# EthernetBridge.net
KiCad netlist of a schematic drawn in Altium Designer
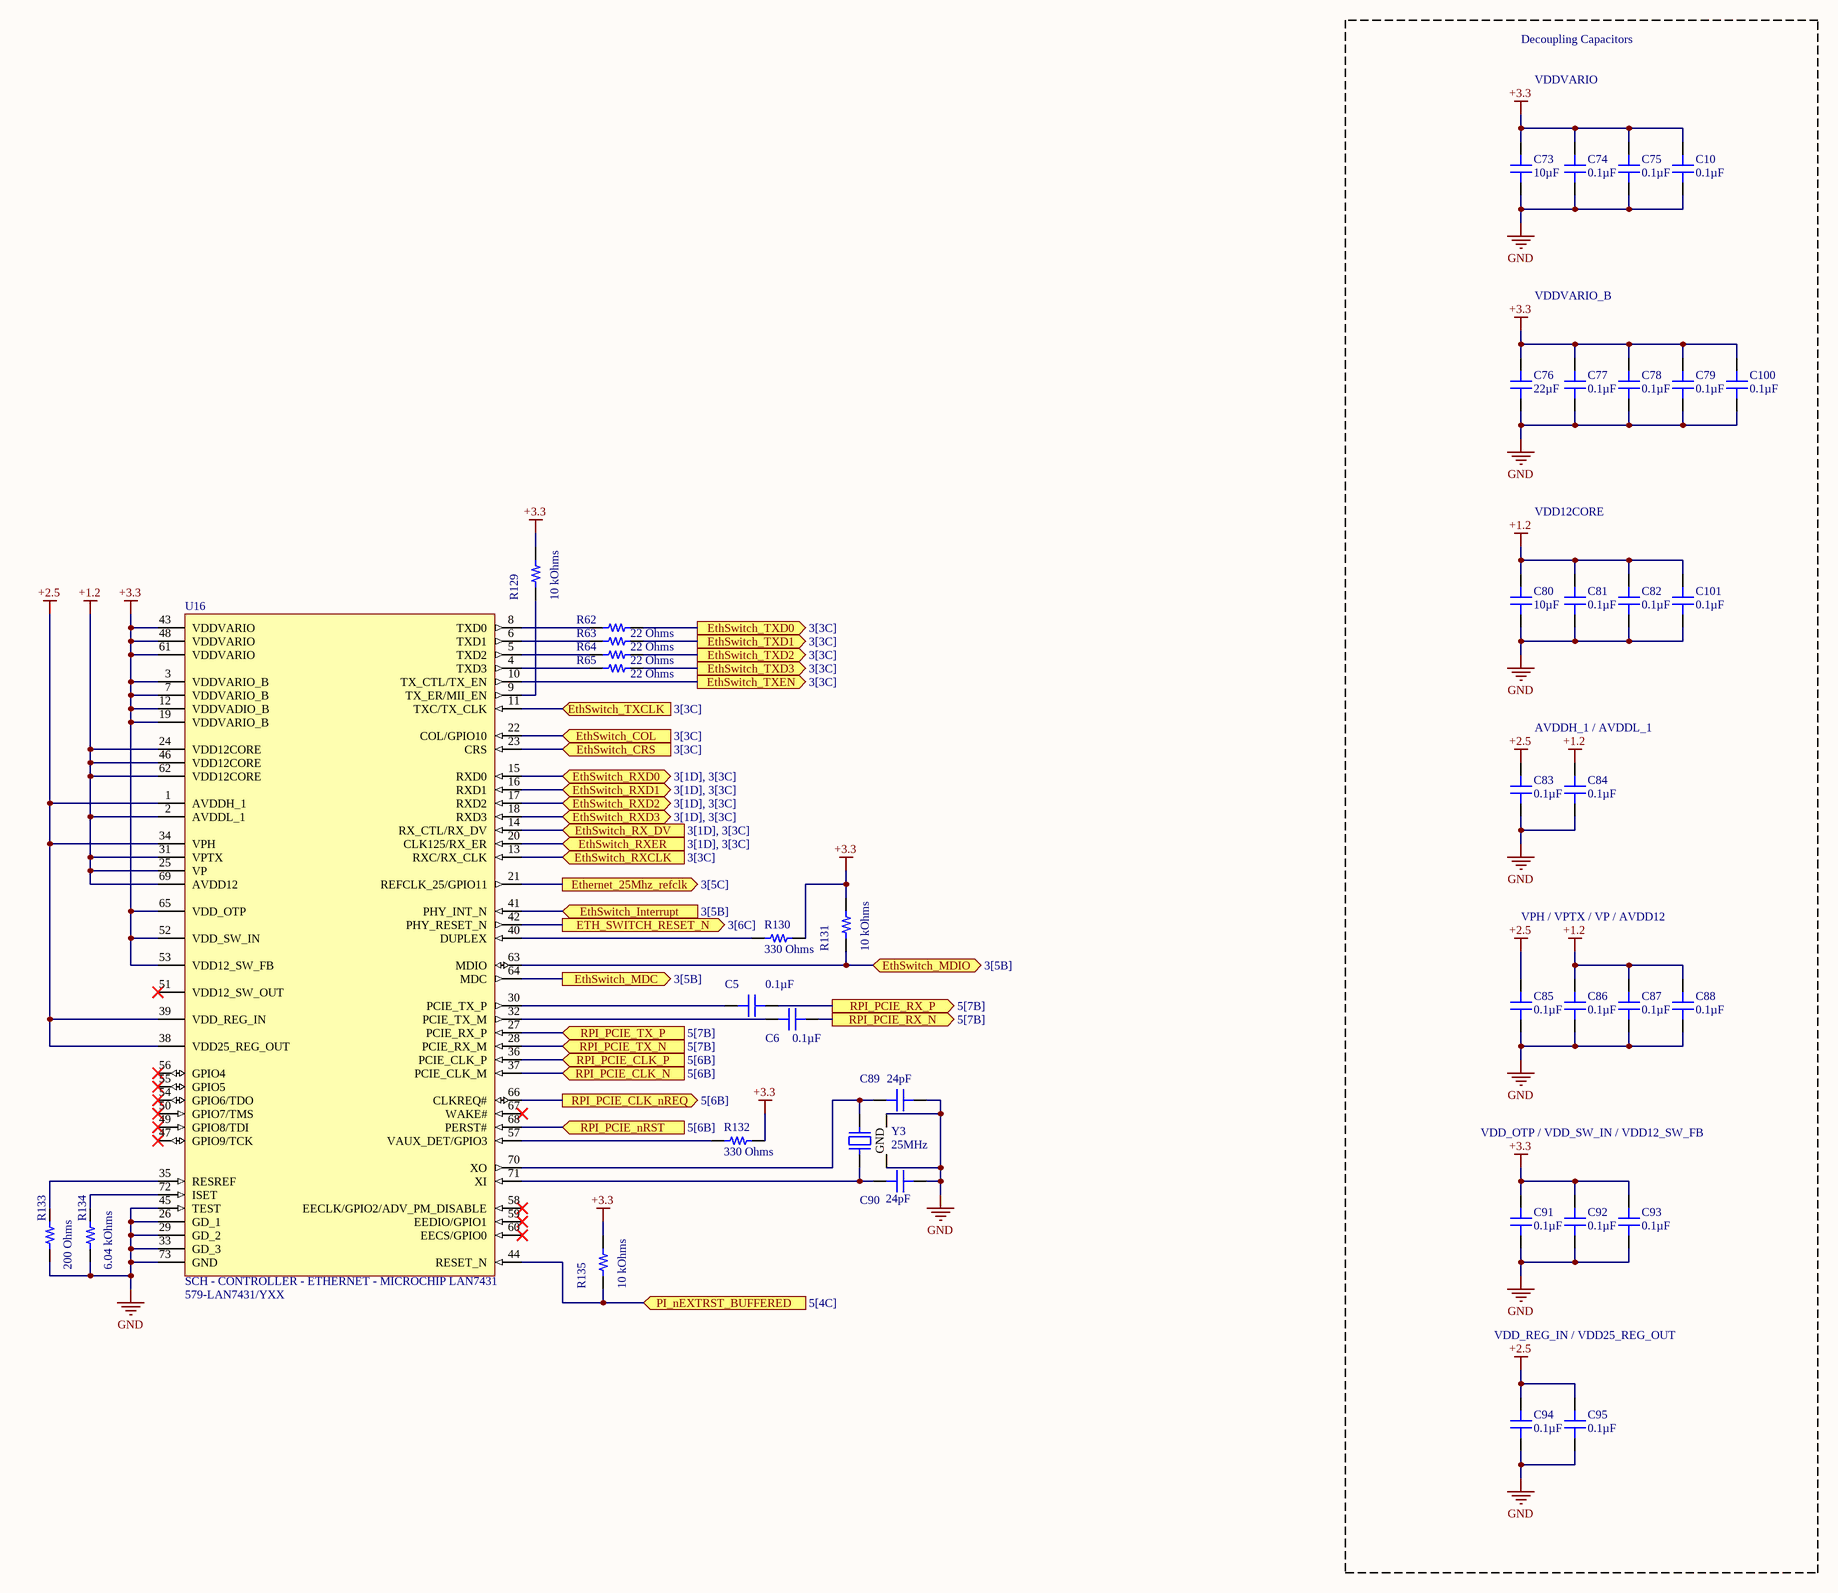
[diagram p0: EthernetBridge.SchDoc]

(export (version "E")
  (design (tool "Eeschema 10.0.6"))
  (components
    (comp (ref "C5")
      (value "0.1µF")
      (footprint "CAP 0603_1608")
      (description "CAP CER 0.1UF 25V X7R 0603")
      (fields
        (field (name "PART NUMBER") "CL10B104KA8WPNC")
        (field (name "MANUFACTURER") "Samsung Electro-Mechanics")
      )
      (libsource (lib "Celestial Altium Library - altium_library") (part "Capacitor"))
    )
    (comp (ref "C6")
      (value "0.1µF")
      (footprint "CAP 0603_1608")
      (description "CAP CER 0.1UF 25V X7R 0603")
      (fields
        (field (name "PART NUMBER") "CL10B104KA8WPNC")
        (field (name "MANUFACTURER") "Samsung Electro-Mechanics")
      )
      (libsource (lib "Celestial Altium Library - altium_library") (part "Capacitor"))
    )
    (comp (ref "C10")
      (value "0.1µF")
      (footprint "CAP 0603_1608")
      (description "CAP CER 0.1UF 25V X7R 0603")
      (fields
        (field (name "PART NUMBER") "CL10B104KA8WPNC")
        (field (name "MANUFACTURER") "Samsung Electro-Mechanics")
      )
      (libsource (lib "Celestial Altium Library - altium_library") (part "Capacitor"))
    )
    (comp (ref "C73")
      (value "10µF")
      (footprint "CAP 0805_2012")
      (description "CAP CER 10UF 16V X5R 0805")
      (fields (field (name "PART NUMBER") "CC0805KKX5R7BB106") (field (name "MANUFACTURER") "Yageo"))
      (libsource (lib "Celestial Altium Library - altium_library") (part "Capacitor"))
    )
    (comp (ref "C74")
      (value "0.1µF")
      (footprint "CAP 0603_1608")
      (description "CAP CER 0.1UF 25V X7R 0603")
      (fields
        (field (name "PART NUMBER") "CL10B104KA8WPNC")
        (field (name "MANUFACTURER") "Samsung Electro-Mechanics")
      )
      (libsource (lib "Celestial Altium Library - altium_library") (part "Capacitor"))
    )
    (comp (ref "C75")
      (value "0.1µF")
      (footprint "CAP 0603_1608")
      (description "CAP CER 0.1UF 25V X7R 0603")
      (fields
        (field (name "PART NUMBER") "CL10B104KA8WPNC")
        (field (name "MANUFACTURER") "Samsung Electro-Mechanics")
      )
      (libsource (lib "Celestial Altium Library - altium_library") (part "Capacitor"))
    )
    (comp (ref "C76")
      (value "22µF")
      (footprint "CAP 0805_2012")
      (description "CAP CER 22UF 10V X5R 0805")
      (fields
        (field (name "PART NUMBER") "CL21A226KPCLRNC")
        (field (name "MANUFACTURER") "Samsung Electro-Mechanics")
      )
      (libsource (lib "Celestial Altium Library - altium_library") (part "Capacitor"))
    )
    (comp (ref "C77")
      (value "0.1µF")
      (footprint "CAP 0603_1608")
      (description "CAP CER 0.1UF 25V X7R 0603")
      (fields
        (field (name "PART NUMBER") "CL10B104KA8WPNC")
        (field (name "MANUFACTURER") "Samsung Electro-Mechanics")
      )
      (libsource (lib "Celestial Altium Library - altium_library") (part "Capacitor"))
    )
    (comp (ref "C78")
      (value "0.1µF")
      (footprint "CAP 0603_1608")
      (description "CAP CER 0.1UF 25V X7R 0603")
      (fields
        (field (name "PART NUMBER") "CL10B104KA8WPNC")
        (field (name "MANUFACTURER") "Samsung Electro-Mechanics")
      )
      (libsource (lib "Celestial Altium Library - altium_library") (part "Capacitor"))
    )
    (comp (ref "C79")
      (value "0.1µF")
      (footprint "CAP 0603_1608")
      (description "CAP CER 0.1UF 25V X7R 0603")
      (fields
        (field (name "PART NUMBER") "CL10B104KA8WPNC")
        (field (name "MANUFACTURER") "Samsung Electro-Mechanics")
      )
      (libsource (lib "Celestial Altium Library - altium_library") (part "Capacitor"))
    )
    (comp (ref "C80")
      (value "10µF")
      (footprint "CAP 0805_2012")
      (description "CAP CER 10UF 16V X5R 0805")
      (fields (field (name "PART NUMBER") "CC0805KKX5R7BB106") (field (name "MANUFACTURER") "Yageo"))
      (libsource (lib "Celestial Altium Library - altium_library") (part "Capacitor"))
    )
    (comp (ref "C81")
      (value "0.1µF")
      (footprint "CAP 0603_1608")
      (description "CAP CER 0.1UF 25V X7R 0603")
      (fields
        (field (name "PART NUMBER") "CL10B104KA8WPNC")
        (field (name "MANUFACTURER") "Samsung Electro-Mechanics")
      )
      (libsource (lib "Celestial Altium Library - altium_library") (part "Capacitor"))
    )
    (comp (ref "C82")
      (value "0.1µF")
      (footprint "CAP 0603_1608")
      (description "CAP CER 0.1UF 25V X7R 0603")
      (fields
        (field (name "PART NUMBER") "CL10B104KA8WPNC")
        (field (name "MANUFACTURER") "Samsung Electro-Mechanics")
      )
      (libsource (lib "Celestial Altium Library - altium_library") (part "Capacitor"))
    )
    (comp (ref "C83")
      (value "0.1µF")
      (footprint "CAP 0603_1608")
      (description "CAP CER 0.1UF 25V X7R 0603")
      (fields
        (field (name "PART NUMBER") "CL10B104KA8WPNC")
        (field (name "MANUFACTURER") "Samsung Electro-Mechanics")
      )
      (libsource (lib "Celestial Altium Library - altium_library") (part "Capacitor"))
    )
    (comp (ref "C84")
      (value "0.1µF")
      (footprint "CAP 0603_1608")
      (description "CAP CER 0.1UF 25V X7R 0603")
      (fields
        (field (name "PART NUMBER") "CL10B104KA8WPNC")
        (field (name "MANUFACTURER") "Samsung Electro-Mechanics")
      )
      (libsource (lib "Celestial Altium Library - altium_library") (part "Capacitor"))
    )
    (comp (ref "C85")
      (value "0.1µF")
      (footprint "CAP 0603_1608")
      (description "CAP CER 0.1UF 25V X7R 0603")
      (fields
        (field (name "PART NUMBER") "CL10B104KA8WPNC")
        (field (name "MANUFACTURER") "Samsung Electro-Mechanics")
      )
      (libsource (lib "Celestial Altium Library - altium_library") (part "Capacitor"))
    )
    (comp (ref "C86")
      (value "0.1µF")
      (footprint "CAP 0603_1608")
      (description "CAP CER 0.1UF 25V X7R 0603")
      (fields
        (field (name "PART NUMBER") "CL10B104KA8WPNC")
        (field (name "MANUFACTURER") "Samsung Electro-Mechanics")
      )
      (libsource (lib "Celestial Altium Library - altium_library") (part "Capacitor"))
    )
    (comp (ref "C87")
      (value "0.1µF")
      (footprint "CAP 0603_1608")
      (description "CAP CER 0.1UF 25V X7R 0603")
      (fields
        (field (name "PART NUMBER") "CL10B104KA8WPNC")
        (field (name "MANUFACTURER") "Samsung Electro-Mechanics")
      )
      (libsource (lib "Celestial Altium Library - altium_library") (part "Capacitor"))
    )
    (comp (ref "C88")
      (value "0.1µF")
      (footprint "CAP 0603_1608")
      (description "CAP CER 0.1UF 25V X7R 0603")
      (fields
        (field (name "PART NUMBER") "CL10B104KA8WPNC")
        (field (name "MANUFACTURER") "Samsung Electro-Mechanics")
      )
      (libsource (lib "Celestial Altium Library - altium_library") (part "Capacitor"))
    )
    (comp (ref "C89")
      (value "24pF")
      (footprint "CAP 0603_1608")
      (description "CAP CER 24PF 50V C0G/NP0 0603")
      (fields
        (field (name "PART NUMBER") "CL10C240JB8NNNC")
        (field (name "MANUFACTURER") "Samsung Electro-Mechanics")
      )
      (libsource (lib "Celestial Altium Library - altium_library") (part "Capacitor"))
    )
    (comp (ref "C90")
      (value "24pF")
      (footprint "CAP 0603_1608")
      (description "CAP CER 24PF 50V C0G/NP0 0603")
      (fields
        (field (name "PART NUMBER") "CL10C240JB8NNNC")
        (field (name "MANUFACTURER") "Samsung Electro-Mechanics")
      )
      (libsource (lib "Celestial Altium Library - altium_library") (part "Capacitor"))
    )
    (comp (ref "C91")
      (value "0.1µF")
      (footprint "CAP 0603_1608")
      (description "CAP CER 0.1UF 25V X7R 0603")
      (fields
        (field (name "PART NUMBER") "CL10B104KA8WPNC")
        (field (name "MANUFACTURER") "Samsung Electro-Mechanics")
      )
      (libsource (lib "Celestial Altium Library - altium_library") (part "Capacitor"))
    )
    (comp (ref "C92")
      (value "0.1µF")
      (footprint "CAP 0603_1608")
      (description "CAP CER 0.1UF 25V X7R 0603")
      (fields
        (field (name "PART NUMBER") "CL10B104KA8WPNC")
        (field (name "MANUFACTURER") "Samsung Electro-Mechanics")
      )
      (libsource (lib "Celestial Altium Library - altium_library") (part "Capacitor"))
    )
    (comp (ref "C93")
      (value "0.1µF")
      (footprint "CAP 0603_1608")
      (description "CAP CER 0.1UF 25V X7R 0603")
      (fields
        (field (name "PART NUMBER") "CL10B104KA8WPNC")
        (field (name "MANUFACTURER") "Samsung Electro-Mechanics")
      )
      (libsource (lib "Celestial Altium Library - altium_library") (part "Capacitor"))
    )
    (comp (ref "C94")
      (value "0.1µF")
      (footprint "CAP 0603_1608")
      (description "CAP CER 0.1UF 25V X7R 0603")
      (fields
        (field (name "PART NUMBER") "CL10B104KA8WPNC")
        (field (name "MANUFACTURER") "Samsung Electro-Mechanics")
      )
      (libsource (lib "Celestial Altium Library - altium_library") (part "Capacitor"))
    )
    (comp (ref "C95")
      (value "0.1µF")
      (footprint "CAP 0603_1608")
      (description "CAP CER 0.1UF 25V X7R 0603")
      (fields
        (field (name "PART NUMBER") "CL10B104KA8WPNC")
        (field (name "MANUFACTURER") "Samsung Electro-Mechanics")
      )
      (libsource (lib "Celestial Altium Library - altium_library") (part "Capacitor"))
    )
    (comp (ref "C100")
      (value "0.1µF")
      (footprint "CAP 0603_1608")
      (description "CAP CER 0.1UF 25V X7R 0603")
      (fields
        (field (name "PART NUMBER") "CL10B104KA8WPNC")
        (field (name "MANUFACTURER") "Samsung Electro-Mechanics")
      )
      (libsource (lib "Celestial Altium Library - altium_library") (part "Capacitor"))
    )
    (comp (ref "C101")
      (value "0.1µF")
      (footprint "CAP 0603_1608")
      (description "CAP CER 0.1UF 25V X7R 0603")
      (fields
        (field (name "PART NUMBER") "CL10B104KA8WPNC")
        (field (name "MANUFACTURER") "Samsung Electro-Mechanics")
      )
      (libsource (lib "Celestial Altium Library - altium_library") (part "Capacitor"))
    )
    (comp (ref "R62")
      (value "22 Ohms")
      (footprint "RES 0603_1608")
      (description "RES 22 OHM 1% 1/10W 0603")
      (fields
        (field (name "PART NUMBER") "RMCF0603FT22R0")
        (field (name "MANUFACTURER") "Stackpole Electronics Inc")
      )
      (libsource (lib "Celestial Altium Library - altium_library") (part "Resistor"))
    )
    (comp (ref "R63")
      (value "22 Ohms")
      (footprint "RES 0603_1608")
      (description "RES 22 OHM 1% 1/10W 0603")
      (fields
        (field (name "PART NUMBER") "RMCF0603FT22R0")
        (field (name "MANUFACTURER") "Stackpole Electronics Inc")
      )
      (libsource (lib "Celestial Altium Library - altium_library") (part "Resistor"))
    )
    (comp (ref "R64")
      (value "22 Ohms")
      (footprint "RES 0603_1608")
      (description "RES 22 OHM 1% 1/10W 0603")
      (fields
        (field (name "PART NUMBER") "RMCF0603FT22R0")
        (field (name "MANUFACTURER") "Stackpole Electronics Inc")
      )
      (libsource (lib "Celestial Altium Library - altium_library") (part "Resistor"))
    )
    (comp (ref "R65")
      (value "22 Ohms")
      (footprint "RES 0603_1608")
      (description "RES 22 OHM 1% 1/10W 0603")
      (fields
        (field (name "PART NUMBER") "RMCF0603FT22R0")
        (field (name "MANUFACTURER") "Stackpole Electronics Inc")
      )
      (libsource (lib "Celestial Altium Library - altium_library") (part "Resistor"))
    )
    (comp (ref "R129")
      (value "10 kOhms")
      (footprint "RES 0603_1608")
      (description "RES 10K OHM 5% 1/10W 0603")
      (fields
        (field (name "PART NUMBER") "RMCF0603JT10K0")
        (field (name "MANUFACTURER") "Stackpole Electronics Inc")
      )
      (libsource (lib "Celestial Altium Library - altium_library") (part "Resistor"))
    )
    (comp (ref "R130")
      (value "330 Ohms")
      (footprint "RES 0603_1608")
      (description "RES 330 OHM 1% 1/10W 0603")
      (fields
        (field (name "PART NUMBER") "RMCF0603FT330R")
        (field (name "MANUFACTURER") "Stackpole Electronics Inc")
      )
      (libsource (lib "Celestial Altium Library - altium_library") (part "Resistor"))
    )
    (comp (ref "R131")
      (value "10 kOhms")
      (footprint "RES 0603_1608")
      (description "RES 10K OHM 5% 1/10W 0603")
      (fields
        (field (name "PART NUMBER") "RMCF0603JT10K0")
        (field (name "MANUFACTURER") "Stackpole Electronics Inc")
      )
      (libsource (lib "Celestial Altium Library - altium_library") (part "Resistor"))
    )
    (comp (ref "R132")
      (value "330 Ohms")
      (footprint "RES 0603_1608")
      (description "RES 330 OHM 1% 1/10W 0603")
      (fields
        (field (name "PART NUMBER") "RMCF0603FT330R")
        (field (name "MANUFACTURER") "Stackpole Electronics Inc")
      )
      (libsource (lib "Celestial Altium Library - altium_library") (part "Resistor"))
    )
    (comp (ref "R133")
      (value "200 Ohms")
      (footprint "RES 0603_1608")
      (description "RES 200 OHM 1% 1/10W 0603")
      (fields
        (field (name "PART NUMBER") "RMCF0603FT200R")
        (field (name "MANUFACTURER") "Stackpole Electronics Inc")
      )
      (libsource (lib "Celestial Altium Library - altium_library") (part "Resistor"))
    )
    (comp (ref "R134")
      (value "6.04 kOhms")
      (footprint "RES 0603_1608")
      (description "RES 6.04K OHM 1% 1/10W 0603")
      (fields
        (field (name "PART NUMBER") "RMCF0603FT6K04")
        (field (name "MANUFACTURER") "Stackpole Electronics Inc")
      )
      (libsource (lib "Celestial Altium Library - altium_library") (part "Resistor"))
    )
    (comp (ref "R135")
      (value "10 kOhms")
      (footprint "RES 0603_1608")
      (description "RES 10K OHM 5% 1/10W 0603")
      (fields
        (field (name "PART NUMBER") "RMCF0603JT10K0")
        (field (name "MANUFACTURER") "Stackpole Electronics Inc")
      )
      (libsource (lib "Celestial Altium Library - altium_library") (part "Resistor"))
    )
    (comp (ref "U16")
      (value "SCH - CONTROLLER - ETHERNET - MICROCHIP LAN7431")
      (footprint "PCB - LEADLESS - QFN - MICROCHIP 72-SQFN")
      (fields (field (name "SUPPLIER PART NUMBER 1") "579-LAN7431/YXX"))
      (libsource (lib "HAB_ICs") (part "SCH - CONTROLLER - ETHERNET - MICROCHIP LAN7431"))
    )
    (comp (ref "Y3")
      (value "25MHz")
      (footprint "EPSON TSX-3225")
      (description "CRYSTAL 25.0000MHZ 18PF SMD")
      (fields (field (name "PART NUMBER") "TSX-3225 25.0000MF20P-C0") (field (name "MANUFACTURER") "EPSON"))
      (libsource (lib "Celestial Altium Library - altium_library") (part "Epson Crystal TSX-3225"))
    )
  )
  (nets
    (net (code "1") (name "+1.2") (class "Default")
      (node (ref "C101") (pin "2") (pinfunction "2_2") (pintype "passive"))
      (node (ref "C80") (pin "2") (pinfunction "2_2") (pintype "passive"))
      (node (ref "C81") (pin "2") (pinfunction "2_2") (pintype "passive"))
      (node (ref "C82") (pin "2") (pinfunction "2_2") (pintype "passive"))
      (node (ref "C84") (pin "2") (pinfunction "2_2") (pintype "passive"))
      (node (ref "C86") (pin "2") (pinfunction "2_2") (pintype "passive"))
      (node (ref "C87") (pin "2") (pinfunction "2_2") (pintype "passive"))
      (node (ref "C88") (pin "2") (pinfunction "2_2") (pintype "passive"))
      (node (ref "U16") (pin "2") (pinfunction "AVDDL_1_2") (pintype "power_in"))
      (node (ref "U16") (pin "24") (pinfunction "VDD12CORE_24") (pintype "power_in"))
      (node (ref "U16") (pin "25") (pinfunction "VP_25") (pintype "power_in"))
      (node (ref "U16") (pin "31") (pinfunction "VPTX_31") (pintype "power_in"))
      (node (ref "U16") (pin "46") (pinfunction "VDD12CORE_46") (pintype "power_in"))
      (node (ref "U16") (pin "62") (pinfunction "VDD12CORE_62") (pintype "power_in"))
      (node (ref "U16") (pin "69") (pinfunction "AVDD12_69") (pintype "power_in"))
    )
    (net (code "2") (name "+2.5") (class "Default")
      (node (ref "C83") (pin "2") (pinfunction "2_2") (pintype "passive"))
      (node (ref "C85") (pin "2") (pinfunction "2_2") (pintype "passive"))
      (node (ref "C94") (pin "2") (pinfunction "2_2") (pintype "passive"))
      (node (ref "C95") (pin "2") (pinfunction "2_2") (pintype "passive"))
      (node (ref "U16") (pin "1") (pinfunction "AVDDH_1_1") (pintype "power_in"))
      (node (ref "U16") (pin "34") (pinfunction "VPH_34") (pintype "power_in"))
      (node (ref "U16") (pin "38") (pinfunction "VDD25_REG_OUT_38") (pintype "power_in"))
      (node (ref "U16") (pin "39") (pinfunction "VDD_REG_IN_39") (pintype "power_in"))
    )
    (net (code "3") (name "+3.3") (class "Default")
      (node (ref "C10") (pin "2") (pinfunction "2_2") (pintype "passive"))
      (node (ref "C100") (pin "2") (pinfunction "2_2") (pintype "passive"))
      (node (ref "C73") (pin "2") (pinfunction "2_2") (pintype "passive"))
      (node (ref "C74") (pin "2") (pinfunction "2_2") (pintype "passive"))
      (node (ref "C75") (pin "2") (pinfunction "2_2") (pintype "passive"))
      (node (ref "C76") (pin "2") (pinfunction "2_2") (pintype "passive"))
      (node (ref "C77") (pin "2") (pinfunction "2_2") (pintype "passive"))
      (node (ref "C78") (pin "2") (pinfunction "2_2") (pintype "passive"))
      (node (ref "C79") (pin "2") (pinfunction "2_2") (pintype "passive"))
      (node (ref "C91") (pin "2") (pinfunction "2_2") (pintype "passive"))
      (node (ref "C92") (pin "2") (pinfunction "2_2") (pintype "passive"))
      (node (ref "C93") (pin "2") (pinfunction "2_2") (pintype "passive"))
      (node (ref "R129") (pin "2") (pinfunction "2_2") (pintype "passive"))
      (node (ref "R130") (pin "1") (pinfunction "1_1") (pintype "passive"))
      (node (ref "R131") (pin "2") (pinfunction "2_2") (pintype "passive"))
      (node (ref "R132") (pin "2") (pinfunction "2_2") (pintype "passive"))
      (node (ref "R135") (pin "2") (pinfunction "2_2") (pintype "passive"))
      (node (ref "U16") (pin "12") (pinfunction "VDDVADIO_B_12") (pintype "power_in"))
      (node (ref "U16") (pin "19") (pinfunction "VDDVARIO_B_19") (pintype "power_in"))
      (node (ref "U16") (pin "3") (pinfunction "VDDVARIO_B_3") (pintype "power_in"))
      (node (ref "U16") (pin "43") (pinfunction "VDDVARIO_43") (pintype "power_in"))
      (node (ref "U16") (pin "48") (pinfunction "VDDVARIO_48") (pintype "power_in"))
      (node (ref "U16") (pin "52") (pinfunction "VDD_SW_IN_52") (pintype "power_in"))
      (node (ref "U16") (pin "53") (pinfunction "VDD12_SW_FB_53") (pintype "power_in"))
      (node (ref "U16") (pin "61") (pinfunction "VDDVARIO_61") (pintype "power_in"))
      (node (ref "U16") (pin "65") (pinfunction "VDD_OTP_65") (pintype "power_in"))
      (node (ref "U16") (pin "7") (pinfunction "VDDVARIO_B_7") (pintype "power_in"))
    )
    (net (code "4") (name "/ETH_SWITCH_RESET_N") (class "Default")
      (node (ref "U16") (pin "42") (pinfunction "PHY_RESET_N_42") (pintype "output"))
    )
    (net (code "5") (name "/EthSwitch_COL") (class "Default")
      (node (ref "U16") (pin "22") (pinfunction "COL/GPIO10_22") (pintype "input"))
    )
    (net (code "6") (name "/EthSwitch_CRS") (class "Default")
      (node (ref "U16") (pin "23") (pinfunction "CRS_23") (pintype "input"))
    )
    (net (code "7") (name "/EthSwitch_Interrupt") (class "Default")
      (node (ref "U16") (pin "41") (pinfunction "PHY_INT_N_41") (pintype "input"))
    )
    (net (code "8") (name "/EthSwitch_MDC") (class "Default")
      (node (ref "U16") (pin "64") (pinfunction "MDC_64") (pintype "output"))
    )
    (net (code "9") (name "/EthSwitch_MDIO") (class "Default")
      (node (ref "R131") (pin "1") (pinfunction "1_1") (pintype "passive"))
      (node (ref "U16") (pin "63") (pinfunction "MDIO_63") (pintype "bidirectional"))
    )
    (net (code "10") (name "/EthSwitch_RXCLK") (class "Default")
      (node (ref "U16") (pin "13") (pinfunction "RXC/RX_CLK_13") (pintype "input"))
    )
    (net (code "11") (name "/EthSwitch_RXD0") (class "Default")
      (node (ref "U16") (pin "15") (pinfunction "RXD0_15") (pintype "input"))
    )
    (net (code "12") (name "/EthSwitch_RXD1") (class "Default")
      (node (ref "U16") (pin "16") (pinfunction "RXD1_16") (pintype "input"))
    )
    (net (code "13") (name "/EthSwitch_RXD2") (class "Default")
      (node (ref "U16") (pin "17") (pinfunction "RXD2_17") (pintype "input"))
    )
    (net (code "14") (name "/EthSwitch_RXD3") (class "Default")
      (node (ref "U16") (pin "18") (pinfunction "RXD3_18") (pintype "input"))
    )
    (net (code "15") (name "/EthSwitch_RXER") (class "Default")
      (node (ref "U16") (pin "20") (pinfunction "CLK125/RX_ER_20") (pintype "input"))
    )
    (net (code "16") (name "/EthSwitch_RX_DV") (class "Default")
      (node (ref "U16") (pin "14") (pinfunction "RX_CTL/RX_DV_14") (pintype "input"))
    )
    (net (code "17") (name "/EthSwitch_TXCLK") (class "Default")
      (node (ref "U16") (pin "11") (pinfunction "TXC/TX_CLK_11") (pintype "input"))
    )
    (net (code "18") (name "/EthSwitch_TXD0") (class "Default")
      (node (ref "R62") (pin "2") (pinfunction "2_2") (pintype "passive"))
    )
    (net (code "19") (name "/EthSwitch_TXD1") (class "Default")
      (node (ref "R63") (pin "2") (pinfunction "2_2") (pintype "passive"))
    )
    (net (code "20") (name "/EthSwitch_TXD2") (class "Default")
      (node (ref "R64") (pin "2") (pinfunction "2_2") (pintype "passive"))
    )
    (net (code "21") (name "/EthSwitch_TXD3") (class "Default")
      (node (ref "R65") (pin "2") (pinfunction "2_2") (pintype "passive"))
    )
    (net (code "22") (name "/EthSwitch_TXEN") (class "Default")
      (node (ref "U16") (pin "10") (pinfunction "TX_CTL/TX_EN_10") (pintype "output"))
    )
    (net (code "23") (name "/Ethernet_25Mhz_refclk") (class "Default")
      (node (ref "U16") (pin "21") (pinfunction "REFCLK_25/GPIO11_21") (pintype "output"))
    )
    (net (code "24") (name "/PI_nEXTRST_BUFFERED") (class "Default")
      (node (ref "R135") (pin "1") (pinfunction "1_1") (pintype "passive"))
      (node (ref "U16") (pin "44") (pinfunction "RESET_N_44") (pintype "input"))
    )
    (net (code "25") (name "/RPI_PCIE_CLK_N") (class "Default")
      (node (ref "U16") (pin "37") (pinfunction "PCIE_CLK_M_37") (pintype "input"))
    )
    (net (code "26") (name "/RPI_PCIE_CLK_P") (class "Default")
      (node (ref "U16") (pin "36") (pinfunction "PCIE_CLK_P_36") (pintype "input"))
    )
    (net (code "27") (name "/RPI_PCIE_CLK_nREQ") (class "Default")
      (node (ref "U16") (pin "66") (pinfunction "CLKREQ#_66") (pintype "bidirectional"))
    )
    (net (code "28") (name "/RPI_PCIE_RX_N") (class "Default")
      (node (ref "C6") (pin "1") (pinfunction "1_1") (pintype "passive"))
    )
    (net (code "29") (name "/RPI_PCIE_RX_P") (class "Default")
      (node (ref "C5") (pin "1") (pinfunction "1_1") (pintype "passive"))
    )
    (net (code "30") (name "/RPI_PCIE_TX_N") (class "Default")
      (node (ref "U16") (pin "28") (pinfunction "PCIE_RX_M_28") (pintype "input"))
    )
    (net (code "31") (name "/RPI_PCIE_TX_P") (class "Default")
      (node (ref "U16") (pin "27") (pinfunction "PCIE_RX_P_27") (pintype "input"))
    )
    (net (code "32") (name "/RPI_PCIE_nRST") (class "Default")
      (node (ref "U16") (pin "68") (pinfunction "PERST#_68") (pintype "input"))
    )
    (net (code "33") (name "GND") (class "Default")
      (node (ref "C10") (pin "1") (pinfunction "1_1") (pintype "passive"))
      (node (ref "C100") (pin "1") (pinfunction "1_1") (pintype "passive"))
      (node (ref "C101") (pin "1") (pinfunction "1_1") (pintype "passive"))
      (node (ref "C73") (pin "1") (pinfunction "1_1") (pintype "passive"))
      (node (ref "C74") (pin "1") (pinfunction "1_1") (pintype "passive"))
      (node (ref "C75") (pin "1") (pinfunction "1_1") (pintype "passive"))
      (node (ref "C76") (pin "1") (pinfunction "1_1") (pintype "passive"))
      (node (ref "C77") (pin "1") (pinfunction "1_1") (pintype "passive"))
      (node (ref "C78") (pin "1") (pinfunction "1_1") (pintype "passive"))
      (node (ref "C79") (pin "1") (pinfunction "1_1") (pintype "passive"))
      (node (ref "C80") (pin "1") (pinfunction "1_1") (pintype "passive"))
      (node (ref "C81") (pin "1") (pinfunction "1_1") (pintype "passive"))
      (node (ref "C82") (pin "1") (pinfunction "1_1") (pintype "passive"))
      (node (ref "C83") (pin "1") (pinfunction "1_1") (pintype "passive"))
      (node (ref "C84") (pin "1") (pinfunction "1_1") (pintype "passive"))
      (node (ref "C85") (pin "1") (pinfunction "1_1") (pintype "passive"))
      (node (ref "C86") (pin "1") (pinfunction "1_1") (pintype "passive"))
      (node (ref "C87") (pin "1") (pinfunction "1_1") (pintype "passive"))
      (node (ref "C88") (pin "1") (pinfunction "1_1") (pintype "passive"))
      (node (ref "C89") (pin "2") (pinfunction "2_2") (pintype "passive"))
      (node (ref "C90") (pin "2") (pinfunction "2_2") (pintype "passive"))
      (node (ref "C91") (pin "1") (pinfunction "1_1") (pintype "passive"))
      (node (ref "C92") (pin "1") (pinfunction "1_1") (pintype "passive"))
      (node (ref "C93") (pin "1") (pinfunction "1_1") (pintype "passive"))
      (node (ref "C94") (pin "1") (pinfunction "1_1") (pintype "passive"))
      (node (ref "C95") (pin "1") (pinfunction "1_1") (pintype "passive"))
      (node (ref "R133") (pin "1") (pinfunction "1_1") (pintype "passive"))
      (node (ref "R134") (pin "1") (pinfunction "1_1") (pintype "passive"))
      (node (ref "U16") (pin "26") (pinfunction "GD_1_26") (pintype "power_in"))
      (node (ref "U16") (pin "29") (pinfunction "GD_2_29") (pintype "power_in"))
      (node (ref "U16") (pin "33") (pinfunction "GD_3_33") (pintype "power_in"))
      (node (ref "U16") (pin "45") (pinfunction "TEST_45") (pintype "input"))
      (node (ref "U16") (pin "73") (pinfunction "GND_73") (pintype "power_in"))
      (node (ref "Y3") (pin "2") (pinfunction "GND_2") (pintype "passive"))
      (node (ref "Y3") (pin "4") (pinfunction "GND_4") (pintype "passive"))
    )
    (net (code "34") (name "Net-(U16-DUPLEX)") (class "Default")
      (node (ref "R130") (pin "2") (pinfunction "2_2") (pintype "passive"))
      (node (ref "U16") (pin "40") (pinfunction "DUPLEX_40") (pintype "input"))
    )
    (net (code "35") (name "Net-(U16-ISET)") (class "Default")
      (node (ref "R134") (pin "2") (pinfunction "2_2") (pintype "passive"))
      (node (ref "U16") (pin "72") (pinfunction "ISET_72") (pintype "input"))
    )
    (net (code "36") (name "Net-(U16-PCIE_TX_M)") (class "Default")
      (node (ref "C6") (pin "2") (pinfunction "2_2") (pintype "passive"))
      (node (ref "U16") (pin "32") (pinfunction "PCIE_TX_M_32") (pintype "output"))
    )
    (net (code "37") (name "Net-(U16-PCIE_TX_P)") (class "Default")
      (node (ref "C5") (pin "2") (pinfunction "2_2") (pintype "passive"))
      (node (ref "U16") (pin "30") (pinfunction "PCIE_TX_P_30") (pintype "output"))
    )
    (net (code "38") (name "Net-(U16-RESREF)") (class "Default")
      (node (ref "R133") (pin "2") (pinfunction "2_2") (pintype "passive"))
      (node (ref "U16") (pin "35") (pinfunction "RESREF_35") (pintype "input"))
    )
    (net (code "39") (name "Net-(U16-TXD0)") (class "Default")
      (node (ref "R62") (pin "1") (pinfunction "1_1") (pintype "passive"))
      (node (ref "U16") (pin "8") (pinfunction "TXD0_8") (pintype "output"))
    )
    (net (code "40") (name "Net-(U16-TXD1)") (class "Default")
      (node (ref "R63") (pin "1") (pinfunction "1_1") (pintype "passive"))
      (node (ref "U16") (pin "6") (pinfunction "TXD1_6") (pintype "output"))
    )
    (net (code "41") (name "Net-(U16-TXD2)") (class "Default")
      (node (ref "R64") (pin "1") (pinfunction "1_1") (pintype "passive"))
      (node (ref "U16") (pin "5") (pinfunction "TXD2_5") (pintype "output"))
    )
    (net (code "42") (name "Net-(U16-TXD3)") (class "Default")
      (node (ref "R65") (pin "1") (pinfunction "1_1") (pintype "passive"))
      (node (ref "U16") (pin "4") (pinfunction "TXD3_4") (pintype "output"))
    )
    (net (code "43") (name "Net-(U16-TX_ER{slash}MII_EN)") (class "Default")
      (node (ref "R129") (pin "1") (pinfunction "1_1") (pintype "passive"))
      (node (ref "U16") (pin "9") (pinfunction "TX_ER/MII_EN_9") (pintype "output"))
    )
    (net (code "44") (name "Net-(U16-VAUX_DET{slash}GPIO3)") (class "Default")
      (node (ref "R132") (pin "1") (pinfunction "1_1") (pintype "passive"))
      (node (ref "U16") (pin "57") (pinfunction "VAUX_DET/GPIO3_57") (pintype "input"))
    )
    (net (code "45") (name "Net-(U16-XI)") (class "Default")
      (node (ref "C90") (pin "1") (pinfunction "1_1") (pintype "passive"))
      (node (ref "U16") (pin "71") (pinfunction "XI_71") (pintype "input"))
      (node (ref "Y3") (pin "1") (pinfunction "1_1") (pintype "passive"))
    )
    (net (code "46") (name "Net-(U16-XO)") (class "Default")
      (node (ref "C89") (pin "1") (pinfunction "1_1") (pintype "passive"))
      (node (ref "U16") (pin "70") (pinfunction "XO_70") (pintype "output"))
      (node (ref "Y3") (pin "3") (pinfunction "3_3") (pintype "passive"))
    )
    (net (code "47") (name "unconnected-(U16-EECLK{slash}GPIO2{slash}ADV_PM_DISABLE-Pad58)") (class "Default")
      (node (ref "U16") (pin "58") (pinfunction "EECLK/GPIO2/ADV_PM_DISABLE_58") (pintype "input+no_connect"))
    )
    (net (code "48") (name "unconnected-(U16-EECS{slash}GPIO0-Pad60)") (class "Default")
      (node (ref "U16") (pin "60") (pinfunction "EECS/GPIO0_60") (pintype "input+no_connect"))
    )
    (net (code "49") (name "unconnected-(U16-EEDIO{slash}GPIO1-Pad59)") (class "Default")
      (node (ref "U16") (pin "59") (pinfunction "EEDIO/GPIO1_59") (pintype "input+no_connect"))
    )
    (net (code "50") (name "unconnected-(U16-GPIO4-Pad56)") (class "Default")
      (node (ref "U16") (pin "56") (pinfunction "GPIO4_56") (pintype "bidirectional+no_connect"))
    )
    (net (code "51") (name "unconnected-(U16-GPIO5-Pad55)") (class "Default")
      (node (ref "U16") (pin "55") (pinfunction "GPIO5_55") (pintype "bidirectional+no_connect"))
    )
    (net (code "52") (name "unconnected-(U16-GPIO6{slash}TDO-Pad54)") (class "Default")
      (node (ref "U16") (pin "54") (pinfunction "GPIO6/TDO_54") (pintype "bidirectional+no_connect"))
    )
    (net (code "53") (name "unconnected-(U16-GPIO7{slash}TMS-Pad50)") (class "Default")
      (node (ref "U16") (pin "50") (pinfunction "GPIO7/TMS_50") (pintype "input+no_connect"))
    )
    (net (code "54") (name "unconnected-(U16-GPIO8{slash}TDI-Pad49)") (class "Default")
      (node (ref "U16") (pin "49") (pinfunction "GPIO8/TDI_49") (pintype "input+no_connect"))
    )
    (net (code "55") (name "unconnected-(U16-GPIO9{slash}TCK-Pad47)") (class "Default")
      (node (ref "U16") (pin "47") (pinfunction "GPIO9/TCK_47") (pintype "bidirectional+no_connect"))
    )
    (net (code "56") (name "unconnected-(U16-VDD12_SW_OUT-Pad51)") (class "Default")
      (node (ref "U16") (pin "51") (pinfunction "VDD12_SW_OUT_51") (pintype "power_in+no_connect"))
    )
    (net (code "57") (name "unconnected-(U16-WAKE#-Pad67)") (class "Default")
      (node (ref "U16") (pin "67") (pinfunction "WAKE#_67") (pintype "input+no_connect"))
    )
  )
)
